# Receiver.net
KiCad netlist of a schematic drawn in Altium Designer
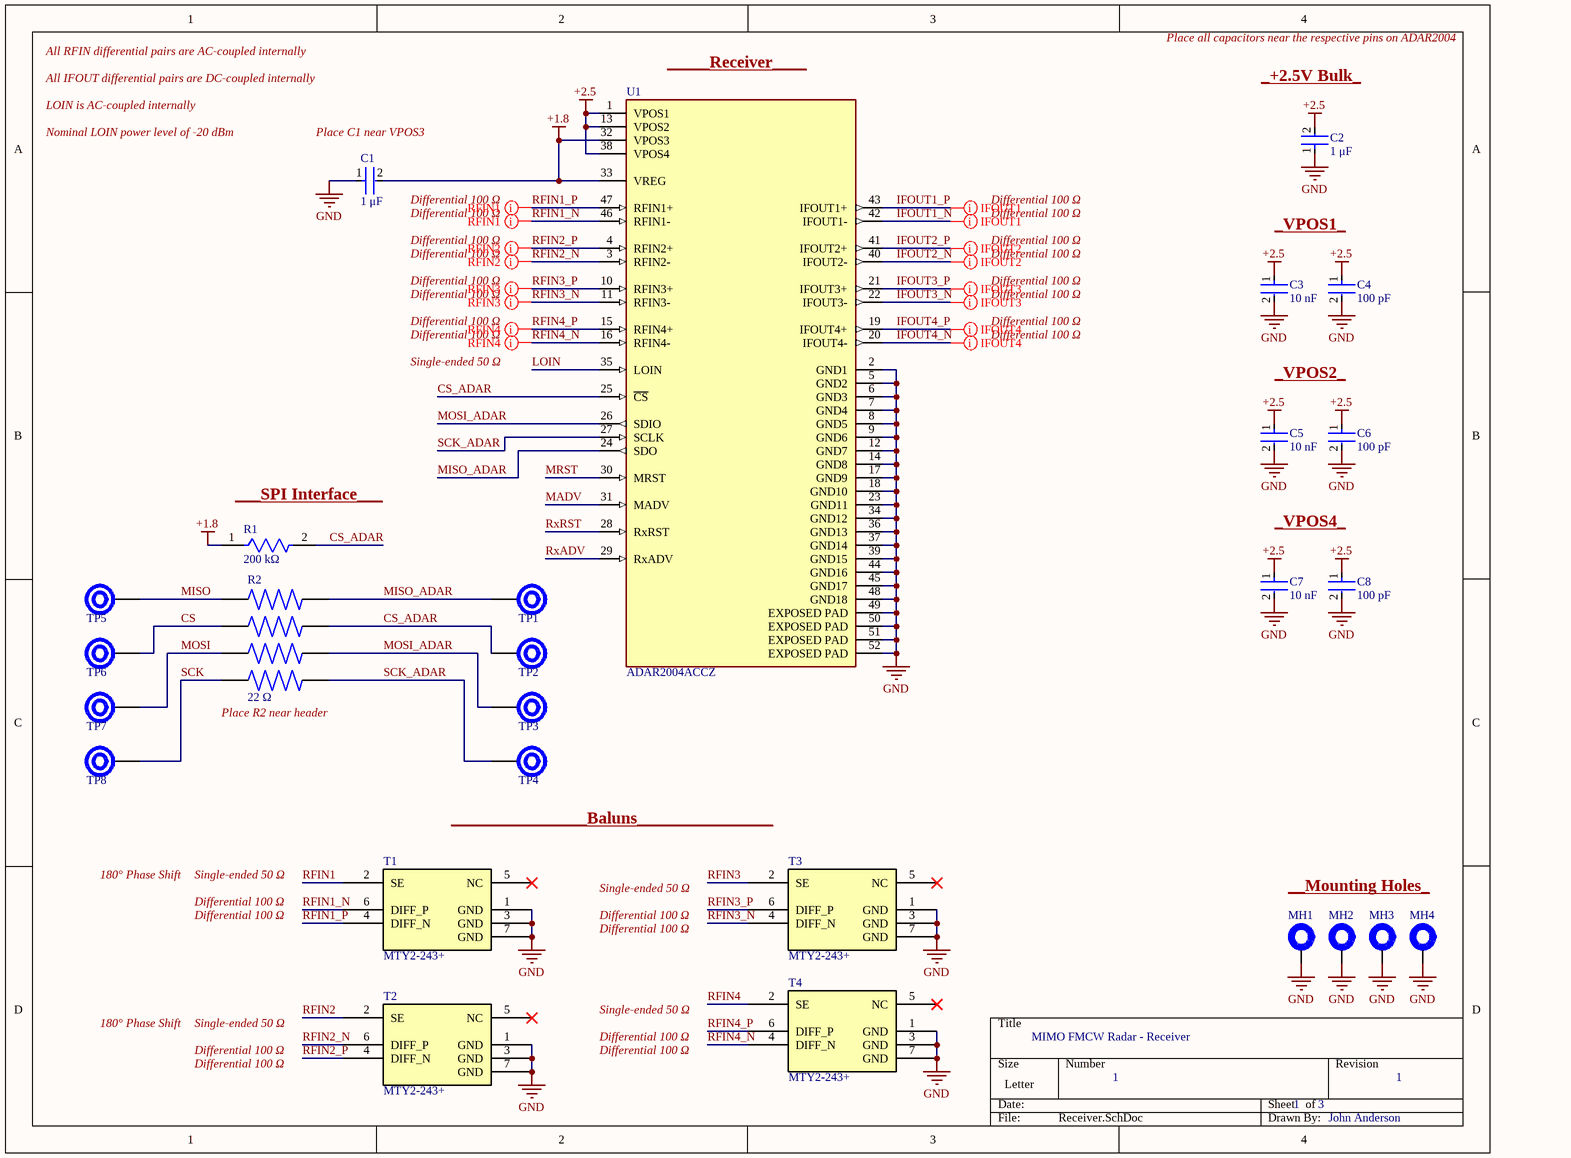
[diagram p0: Receiver.SchDoc]

(export (version "E")
  (design (tool "Eeschema 10.0.6"))
  (components
    (comp (ref "C1")
      (value "1 μF")
      (footprint "FP-0603-L_1_6_0_15-W_0_8-MFG")
      (libsource (lib "Power Pullers") (part "11868f565c42a9108669ba33697ecf6"))
    )
    (comp (ref "C2")
      (value "1 μF")
      (footprint "FP-0603-L_1_6_0_15-W_0_8-MFG")
      (libsource (lib "Power Pullers") (part "11868f565c42a9108669ba33697ecf6"))
    )
    (comp (ref "C3")
      (value "10 nF")
      (footprint "CGA3E2X7R1H103K080AA-Footprint-1")
      (description "CGA Series 0603 10 nF 50 V ±10 % Tolerance X7R SMT Multilayer Ceramic Capacitor")
      (fields (field (name "TOLERANCE") "10%"))
      (libsource (lib "Power Pullers") (part "CGA3E2X7R1H103K080AA-Symbol-1"))
    )
    (comp (ref "C4")
      (value "100 pF")
      (footprint "FP-C0603C-CF-IPC_C")
      (description "Multilayer Ceramic Capacitors MLCC – SMD/SMT; KEMET; C0603C101J5GACTU; 100 pF; 0603; 50 V; 50 V")
      (fields (field (name "VOLTAGE") "50V") (field (name "TOLERANCE") "5%"))
      (libsource (lib "Power Pullers") (part "b4654b650e69147ec39a6b967a45e02"))
    )
    (comp (ref "C5")
      (value "10 nF")
      (footprint "CGA3E2X7R1H103K080AA-Footprint-1")
      (description "CGA Series 0603 10 nF 50 V ±10 % Tolerance X7R SMT Multilayer Ceramic Capacitor")
      (fields (field (name "TOLERANCE") "10%"))
      (libsource (lib "Power Pullers") (part "CGA3E2X7R1H103K080AA-Symbol-1"))
    )
    (comp (ref "C6")
      (value "100 pF")
      (footprint "FP-C0603C-CF-IPC_C")
      (description "Multilayer Ceramic Capacitors MLCC – SMD/SMT; KEMET; C0603C101J5GACTU; 100 pF; 0603; 50 V; 50 V")
      (fields (field (name "VOLTAGE") "50V") (field (name "TOLERANCE") "5%"))
      (libsource (lib "Power Pullers") (part "b4654b650e69147ec39a6b967a45e02"))
    )
    (comp (ref "C7")
      (value "10 nF")
      (footprint "CGA3E2X7R1H103K080AA-Footprint-1")
      (description "CGA Series 0603 10 nF 50 V ±10 % Tolerance X7R SMT Multilayer Ceramic Capacitor")
      (fields (field (name "TOLERANCE") "10%"))
      (libsource (lib "Power Pullers") (part "CGA3E2X7R1H103K080AA-Symbol-1"))
    )
    (comp (ref "C8")
      (value "100 pF")
      (footprint "FP-C0603C-CF-IPC_C")
      (description "Multilayer Ceramic Capacitors MLCC – SMD/SMT; KEMET; C0603C101J5GACTU; 100 pF; 0603; 50 V; 50 V")
      (fields (field (name "VOLTAGE") "50V") (field (name "TOLERANCE") "5%"))
      (libsource (lib "Power Pullers") (part "b4654b650e69147ec39a6b967a45e02"))
    )
    (comp (ref "MH1")
      (value "M3 Plated Mounting Hole - Loose")
      (footprint "M3 Plated Mounting Hole-Footprint-1")
      (description "Plated M3 mounting hole with loose tolerance. 3.6 mm hole diameter, 4.6 mm plated diameter.")
      (libsource (lib "Power Pullers") (part "M3 Plated Mounting Hole-Symbol-1"))
    )
    (comp (ref "MH2")
      (value "M3 Plated Mounting Hole - Loose")
      (footprint "M3 Plated Mounting Hole-Footprint-1")
      (description "Plated M3 mounting hole with loose tolerance. 3.6 mm hole diameter, 4.6 mm plated diameter.")
      (libsource (lib "Power Pullers") (part "M3 Plated Mounting Hole-Symbol-1"))
    )
    (comp (ref "MH3")
      (value "M3 Plated Mounting Hole - Loose")
      (footprint "M3 Plated Mounting Hole-Footprint-1")
      (description "Plated M3 mounting hole with loose tolerance. 3.6 mm hole diameter, 4.6 mm plated diameter.")
      (libsource (lib "Power Pullers") (part "M3 Plated Mounting Hole-Symbol-1"))
    )
    (comp (ref "MH4")
      (value "M3 Plated Mounting Hole - Loose")
      (footprint "M3 Plated Mounting Hole-Footprint-1")
      (description "Plated M3 mounting hole with loose tolerance. 3.6 mm hole diameter, 4.6 mm plated diameter.")
      (libsource (lib "Power Pullers") (part "M3 Plated Mounting Hole-Symbol-1"))
    )
    (comp (ref "R1")
      (value "200 kΩ")
      (footprint "FP-RG1608-IPC_C")
      (description "Res Thin Film 0603 200K Ohm 0.1% 0.1W(1/10W) ±25ppm/C Sulfur Resistant Pad SMD Automotive T/R")
      (fields (field (name "TOLERANCE") "0.1%"))
      (libsource (lib "Power Pullers") (part "1029c3af85768c4190bb7ad29bc67b5"))
    )
    (comp (ref "R2")
      (value "22 Ω")
      (footprint "CAY16-22R0F4LF-Footprint-1")
      (description "Res Thick Film Array 22 Ohm 1% 0.25W(1/4W) ±200ppm/C ISOL 8-Pin 1206(4 X 0603) Convex SMD T/R")
      (fields (field (name "TOLERANCE") "1%"))
      (libsource (lib "Power Pullers") (part "CAY16-22R0F4LF-Symbol-1"))
    )
    (comp (ref "T1")
      (value "MTY2-243+")
      (footprint "MTY2-243+-Footprint-1")
      (description "RF Transformer, 10000MHz Min, 24000MHz Max")
      (libsource (lib "Power Pullers") (part "MTY2-243+-Symbol-1"))
    )
    (comp (ref "T2")
      (value "MTY2-243+")
      (footprint "MTY2-243+-Footprint-1")
      (description "RF Transformer, 10000MHz Min, 24000MHz Max")
      (libsource (lib "Power Pullers") (part "MTY2-243+-Symbol-1"))
    )
    (comp (ref "T3")
      (value "MTY2-243+")
      (footprint "MTY2-243+-Footprint-1")
      (description "RF Transformer, 10000MHz Min, 24000MHz Max")
      (libsource (lib "Power Pullers") (part "MTY2-243+-Symbol-1"))
    )
    (comp (ref "T4")
      (value "MTY2-243+")
      (footprint "MTY2-243+-Footprint-1")
      (description "RF Transformer, 10000MHz Min, 24000MHz Max")
      (libsource (lib "Power Pullers") (part "MTY2-243+-Symbol-1"))
    )
    (comp (ref "TP1")
      (value "Test Point - 32 mil")
      (footprint "Test Point - 32 mil-Footprint-1")
      (description "32 mil (0.8 mm) test point.")
      (libsource (lib "Power Pullers") (part "Test Point - 32 mil-Symbol-1"))
    )
    (comp (ref "TP2")
      (value "Test Point - 32 mil")
      (footprint "Test Point - 32 mil-Footprint-1")
      (description "32 mil (0.8 mm) test point.")
      (libsource (lib "Power Pullers") (part "Test Point - 32 mil-Symbol-1"))
    )
    (comp (ref "TP3")
      (value "Test Point - 32 mil")
      (footprint "Test Point - 32 mil-Footprint-1")
      (description "32 mil (0.8 mm) test point.")
      (libsource (lib "Power Pullers") (part "Test Point - 32 mil-Symbol-1"))
    )
    (comp (ref "TP4")
      (value "Test Point - 32 mil")
      (footprint "Test Point - 32 mil-Footprint-1")
      (description "32 mil (0.8 mm) test point.")
      (libsource (lib "Power Pullers") (part "Test Point - 32 mil-Symbol-1"))
    )
    (comp (ref "TP5")
      (value "Test Point - 32 mil")
      (footprint "Test Point - 32 mil-Footprint-1")
      (description "32 mil (0.8 mm) test point.")
      (libsource (lib "Power Pullers") (part "Test Point - 32 mil-Symbol-1"))
    )
    (comp (ref "TP6")
      (value "Test Point - 32 mil")
      (footprint "Test Point - 32 mil-Footprint-1")
      (description "32 mil (0.8 mm) test point.")
      (libsource (lib "Power Pullers") (part "Test Point - 32 mil-Symbol-1"))
    )
    (comp (ref "TP7")
      (value "Test Point - 32 mil")
      (footprint "Test Point - 32 mil-Footprint-1")
      (description "32 mil (0.8 mm) test point.")
      (libsource (lib "Power Pullers") (part "Test Point - 32 mil-Symbol-1"))
    )
    (comp (ref "TP8")
      (value "Test Point - 32 mil")
      (footprint "Test Point - 32 mil-Footprint-1")
      (description "32 mil (0.8 mm) test point.")
      (libsource (lib "Power Pullers") (part "Test Point - 32 mil-Symbol-1"))
    )
    (comp (ref "U1")
      (value "ADAR2004ACCZ")
      (footprint "FP-CC-48-2-MFG")
      (description "10 GHz to 40 GHz, 4-Channel Rx Mixer with 4× LO Multiplier/Filter")
      (libsource (lib "Power Pullers") (part "118717e4abb16449a089c68d6e54be3"))
    )
  )
  (nets
    (net (code "1") (name "+1.8") (class "Default")
      (node (ref "C1") (pin "2") (pinfunction "2_2") (pintype "passive"))
      (node (ref "R1") (pin "1") (pinfunction "1_1") (pintype "passive"))
      (node (ref "U1") (pin "32") (pinfunction "VPOS3_32") (pintype "power_in"))
      (node (ref "U1") (pin "33") (pinfunction "VREG_33") (pintype "power_in"))
    )
    (net (code "2") (name "+2.5") (class "Default")
      (node (ref "C2") (pin "2") (pinfunction "2_2") (pintype "passive"))
      (node (ref "C3") (pin "1") (pinfunction "1_1") (pintype "passive"))
      (node (ref "C4") (pin "1") (pinfunction "1_1") (pintype "passive"))
      (node (ref "C5") (pin "1") (pinfunction "1_1") (pintype "passive"))
      (node (ref "C6") (pin "1") (pinfunction "1_1") (pintype "passive"))
      (node (ref "C7") (pin "1") (pinfunction "1_1") (pintype "passive"))
      (node (ref "C8") (pin "1") (pinfunction "1_1") (pintype "passive"))
      (node (ref "U1") (pin "1") (pinfunction "VPOS1_1") (pintype "power_in"))
      (node (ref "U1") (pin "13") (pinfunction "VPOS2_13") (pintype "power_in"))
      (node (ref "U1") (pin "38") (pinfunction "VPOS4_38") (pintype "power_in"))
    )
    (net (code "3") (name "/CS") (class "Default")
      (node (ref "R2") (pin "2") (pinfunction "2_2") (pintype "passive"))
      (node (ref "TP6") (pin "1") (pinfunction "1_1") (pintype "passive"))
    )
    (net (code "4") (name "/CS_ADAR") (class "Default")
      (node (ref "R1") (pin "2") (pinfunction "2_2") (pintype "passive"))
      (node (ref "R2") (pin "7") (pinfunction "7_7") (pintype "passive"))
      (node (ref "TP2") (pin "1") (pinfunction "1_1") (pintype "passive"))
      (node (ref "U1") (pin "25") (pinfunction "~{CS}_25") (pintype "input"))
    )
    (net (code "5") (name "/IFOUT1_N") (class "Default")
      (node (ref "U1") (pin "42") (pinfunction "IFOUT1-_42") (pintype "output"))
    )
    (net (code "6") (name "/IFOUT1_P") (class "Default")
      (node (ref "U1") (pin "43") (pinfunction "IFOUT1+_43") (pintype "output"))
    )
    (net (code "7") (name "/IFOUT2_N") (class "Default")
      (node (ref "U1") (pin "40") (pinfunction "IFOUT2-_40") (pintype "output"))
    )
    (net (code "8") (name "/IFOUT2_P") (class "Default")
      (node (ref "U1") (pin "41") (pinfunction "IFOUT2+_41") (pintype "output"))
    )
    (net (code "9") (name "/IFOUT3_N") (class "Default")
      (node (ref "U1") (pin "22") (pinfunction "IFOUT3-_22") (pintype "output"))
    )
    (net (code "10") (name "/IFOUT3_P") (class "Default")
      (node (ref "U1") (pin "21") (pinfunction "IFOUT3+_21") (pintype "output"))
    )
    (net (code "11") (name "/IFOUT4_N") (class "Default")
      (node (ref "U1") (pin "20") (pinfunction "IFOUT4-_20") (pintype "output"))
    )
    (net (code "12") (name "/IFOUT4_P") (class "Default")
      (node (ref "U1") (pin "19") (pinfunction "IFOUT4+_19") (pintype "output"))
    )
    (net (code "13") (name "/LOIN") (class "Default")
      (node (ref "U1") (pin "35") (pinfunction "LOIN_35") (pintype "input"))
    )
    (net (code "14") (name "/MADV") (class "Default")
      (node (ref "U1") (pin "31") (pinfunction "MADV_31") (pintype "input"))
    )
    (net (code "15") (name "/MISO") (class "Default")
      (node (ref "R2") (pin "1") (pinfunction "1_1") (pintype "passive"))
      (node (ref "TP5") (pin "1") (pinfunction "1_1") (pintype "passive"))
    )
    (net (code "16") (name "/MISO_ADAR") (class "Default")
      (node (ref "R2") (pin "8") (pinfunction "8_8") (pintype "passive"))
      (node (ref "TP1") (pin "1") (pinfunction "1_1") (pintype "passive"))
      (node (ref "U1") (pin "24") (pinfunction "SDO_24") (pintype "output"))
    )
    (net (code "17") (name "/MOSI") (class "Default")
      (node (ref "R2") (pin "3") (pinfunction "3_3") (pintype "passive"))
      (node (ref "TP7") (pin "1") (pinfunction "1_1") (pintype "passive"))
    )
    (net (code "18") (name "/MOSI_ADAR") (class "Default")
      (node (ref "R2") (pin "6") (pinfunction "6_6") (pintype "passive"))
      (node (ref "TP3") (pin "1") (pinfunction "1_1") (pintype "passive"))
      (node (ref "U1") (pin "26") (pinfunction "SDIO_26") (pintype "output"))
    )
    (net (code "19") (name "/MRST") (class "Default")
      (node (ref "U1") (pin "30") (pinfunction "MRST_30") (pintype "input"))
    )
    (net (code "20") (name "/RFIN1") (class "Default")
      (node (ref "T1") (pin "2") (pinfunction "SE_2") (pintype "passive"))
    )
    (net (code "21") (name "/RFIN1_N") (class "Default")
      (node (ref "T1") (pin "6") (pinfunction "DIFF_P_6") (pintype "passive"))
      (node (ref "U1") (pin "46") (pinfunction "RFIN1-_46") (pintype "input"))
    )
    (net (code "22") (name "/RFIN1_P") (class "Default")
      (node (ref "T1") (pin "4") (pinfunction "DIFF_N_4") (pintype "passive"))
      (node (ref "U1") (pin "47") (pinfunction "RFIN1+_47") (pintype "input"))
    )
    (net (code "23") (name "/RFIN2") (class "Default")
      (node (ref "T2") (pin "2") (pinfunction "SE_2") (pintype "passive"))
    )
    (net (code "24") (name "/RFIN2_N") (class "Default")
      (node (ref "T2") (pin "6") (pinfunction "DIFF_P_6") (pintype "passive"))
      (node (ref "U1") (pin "3") (pinfunction "RFIN2-_3") (pintype "input"))
    )
    (net (code "25") (name "/RFIN2_P") (class "Default")
      (node (ref "T2") (pin "4") (pinfunction "DIFF_N_4") (pintype "passive"))
      (node (ref "U1") (pin "4") (pinfunction "RFIN2+_4") (pintype "input"))
    )
    (net (code "26") (name "/RFIN3") (class "Default")
      (node (ref "T3") (pin "2") (pinfunction "SE_2") (pintype "passive"))
    )
    (net (code "27") (name "/RFIN3_N") (class "Default")
      (node (ref "T3") (pin "4") (pinfunction "DIFF_N_4") (pintype "passive"))
      (node (ref "U1") (pin "11") (pinfunction "RFIN3-_11") (pintype "input"))
    )
    (net (code "28") (name "/RFIN3_P") (class "Default")
      (node (ref "T3") (pin "6") (pinfunction "DIFF_P_6") (pintype "passive"))
      (node (ref "U1") (pin "10") (pinfunction "RFIN3+_10") (pintype "input"))
    )
    (net (code "29") (name "/RFIN4") (class "Default")
      (node (ref "T4") (pin "2") (pinfunction "SE_2") (pintype "passive"))
    )
    (net (code "30") (name "/RFIN4_N") (class "Default")
      (node (ref "T4") (pin "4") (pinfunction "DIFF_N_4") (pintype "passive"))
      (node (ref "U1") (pin "16") (pinfunction "RFIN4-_16") (pintype "input"))
    )
    (net (code "31") (name "/RFIN4_P") (class "Default")
      (node (ref "T4") (pin "6") (pinfunction "DIFF_P_6") (pintype "passive"))
      (node (ref "U1") (pin "15") (pinfunction "RFIN4+_15") (pintype "input"))
    )
    (net (code "32") (name "/RxADV") (class "Default")
      (node (ref "U1") (pin "29") (pinfunction "RxADV_29") (pintype "input"))
    )
    (net (code "33") (name "/RxRST") (class "Default")
      (node (ref "U1") (pin "28") (pinfunction "RxRST_28") (pintype "input"))
    )
    (net (code "34") (name "/SCK") (class "Default")
      (node (ref "R2") (pin "4") (pinfunction "4_4") (pintype "passive"))
      (node (ref "TP8") (pin "1") (pinfunction "1_1") (pintype "passive"))
    )
    (net (code "35") (name "/SCK_ADAR") (class "Default")
      (node (ref "R2") (pin "5") (pinfunction "5_5") (pintype "passive"))
      (node (ref "TP4") (pin "1") (pinfunction "1_1") (pintype "passive"))
      (node (ref "U1") (pin "27") (pinfunction "SCLK_27") (pintype "input"))
    )
    (net (code "36") (name "GND") (class "Default")
      (node (ref "C1") (pin "1") (pinfunction "1_1") (pintype "passive"))
      (node (ref "C2") (pin "1") (pinfunction "1_1") (pintype "passive"))
      (node (ref "C3") (pin "2") (pinfunction "2_2") (pintype "passive"))
      (node (ref "C4") (pin "2") (pinfunction "2_2") (pintype "passive"))
      (node (ref "C5") (pin "2") (pinfunction "2_2") (pintype "passive"))
      (node (ref "C6") (pin "2") (pinfunction "2_2") (pintype "passive"))
      (node (ref "C7") (pin "2") (pinfunction "2_2") (pintype "passive"))
      (node (ref "C8") (pin "2") (pinfunction "2_2") (pintype "passive"))
      (node (ref "MH1") (pin "1") (pinfunction "1_1") (pintype "passive"))
      (node (ref "MH2") (pin "1") (pinfunction "1_1") (pintype "passive"))
      (node (ref "MH3") (pin "1") (pinfunction "1_1") (pintype "passive"))
      (node (ref "MH4") (pin "1") (pinfunction "1_1") (pintype "passive"))
      (node (ref "T1") (pin "1") (pinfunction "GND_1") (pintype "power_in"))
      (node (ref "T1") (pin "3") (pinfunction "GND_3") (pintype "power_in"))
      (node (ref "T1") (pin "7") (pinfunction "GND_7") (pintype "power_in"))
      (node (ref "T2") (pin "1") (pinfunction "GND_1") (pintype "power_in"))
      (node (ref "T2") (pin "3") (pinfunction "GND_3") (pintype "power_in"))
      (node (ref "T2") (pin "7") (pinfunction "GND_7") (pintype "power_in"))
      (node (ref "T3") (pin "1") (pinfunction "GND_1") (pintype "power_in"))
      (node (ref "T3") (pin "3") (pinfunction "GND_3") (pintype "power_in"))
      (node (ref "T3") (pin "7") (pinfunction "GND_7") (pintype "power_in"))
      (node (ref "T4") (pin "1") (pinfunction "GND_1") (pintype "power_in"))
      (node (ref "T4") (pin "3") (pinfunction "GND_3") (pintype "power_in"))
      (node (ref "T4") (pin "7") (pinfunction "GND_7") (pintype "power_in"))
      (node (ref "U1") (pin "12") (pinfunction "GND7_12") (pintype "power_in"))
      (node (ref "U1") (pin "14") (pinfunction "GND8_14") (pintype "power_in"))
      (node (ref "U1") (pin "17") (pinfunction "GND9_17") (pintype "power_in"))
      (node (ref "U1") (pin "18") (pinfunction "GND10_18") (pintype "power_in"))
      (node (ref "U1") (pin "2") (pinfunction "GND1_2") (pintype "power_in"))
      (node (ref "U1") (pin "23") (pinfunction "GND11_23") (pintype "power_in"))
      (node (ref "U1") (pin "34") (pinfunction "GND12_34") (pintype "power_in"))
      (node (ref "U1") (pin "36") (pinfunction "GND13_36") (pintype "power_in"))
      (node (ref "U1") (pin "37") (pinfunction "GND14_37") (pintype "power_in"))
      (node (ref "U1") (pin "39") (pinfunction "GND15_39") (pintype "power_in"))
      (node (ref "U1") (pin "44") (pinfunction "GND16_44") (pintype "power_in"))
      (node (ref "U1") (pin "45") (pinfunction "GND17_45") (pintype "power_in"))
      (node (ref "U1") (pin "48") (pinfunction "GND18_48") (pintype "power_in"))
      (node (ref "U1") (pin "49") (pinfunction "EXPOSED_PAD_49") (pintype "power_in"))
      (node (ref "U1") (pin "5") (pinfunction "GND2_5") (pintype "power_in"))
      (node (ref "U1") (pin "50") (pinfunction "EXPOSED_PAD_50") (pintype "power_in"))
      (node (ref "U1") (pin "51") (pinfunction "EXPOSED_PAD_51") (pintype "power_in"))
      (node (ref "U1") (pin "52") (pinfunction "EXPOSED_PAD_52") (pintype "power_in"))
      (node (ref "U1") (pin "6") (pinfunction "GND3_6") (pintype "power_in"))
      (node (ref "U1") (pin "7") (pinfunction "GND4_7") (pintype "power_in"))
      (node (ref "U1") (pin "8") (pinfunction "GND5_8") (pintype "power_in"))
      (node (ref "U1") (pin "9") (pinfunction "GND6_9") (pintype "power_in"))
    )
    (net (code "37") (name "unconnected-(T1-NC-Pad5)") (class "Default")
      (node (ref "T1") (pin "5") (pinfunction "NC_5") (pintype "passive+no_connect"))
    )
    (net (code "38") (name "unconnected-(T2-NC-Pad5)") (class "Default")
      (node (ref "T2") (pin "5") (pinfunction "NC_5") (pintype "passive+no_connect"))
    )
    (net (code "39") (name "unconnected-(T3-NC-Pad5)") (class "Default")
      (node (ref "T3") (pin "5") (pinfunction "NC_5") (pintype "passive+no_connect"))
    )
    (net (code "40") (name "unconnected-(T4-NC-Pad5)") (class "Default")
      (node (ref "T4") (pin "5") (pinfunction "NC_5") (pintype "passive+no_connect"))
    )
  )
)
